# ADC.net
KiCad netlist of a schematic drawn in Altium Designer
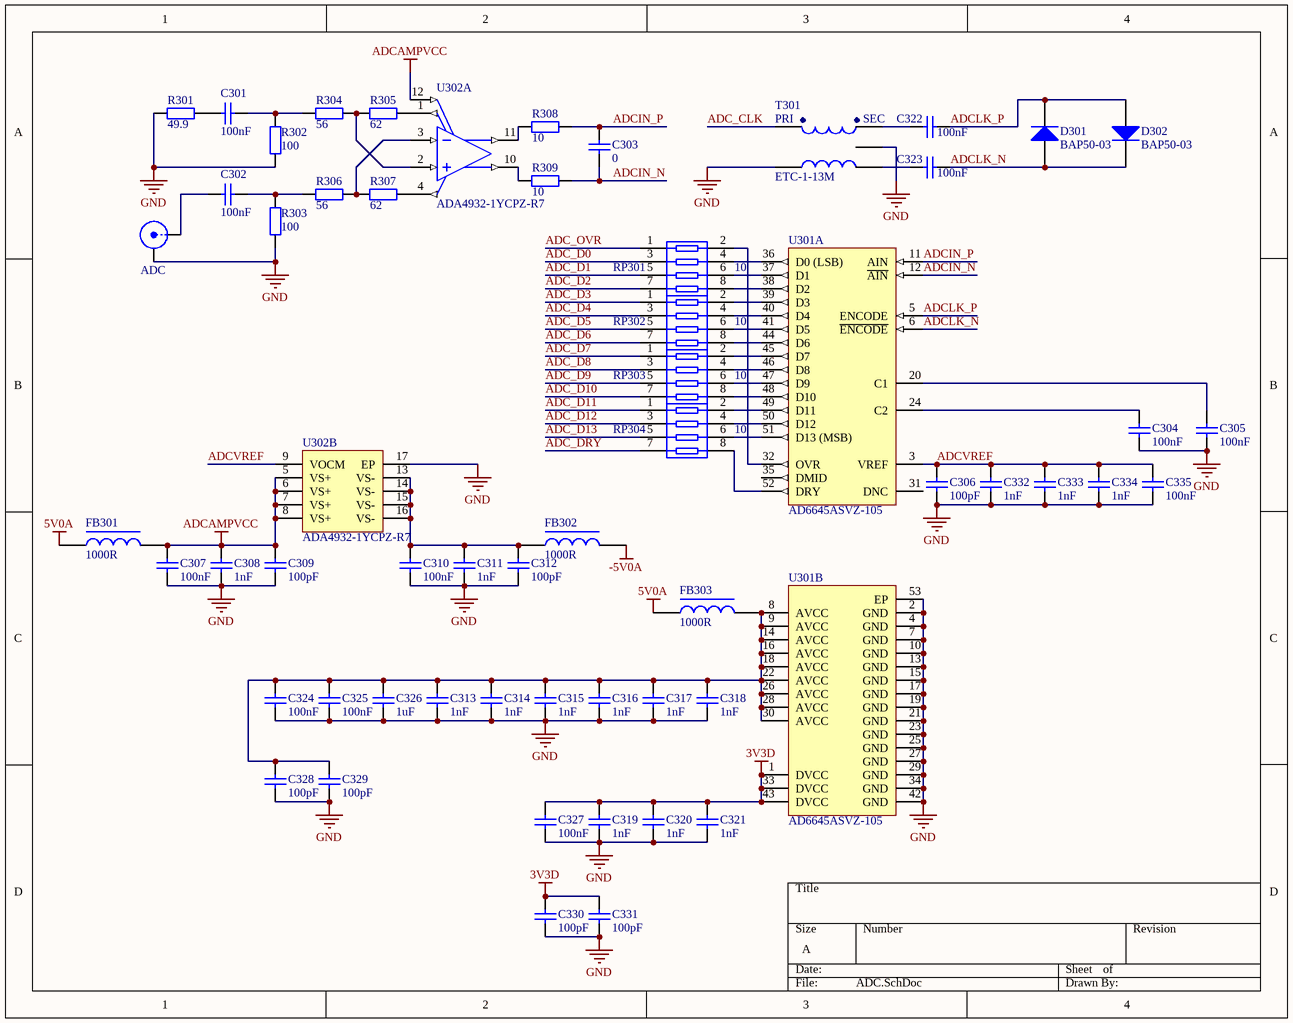
[diagram p0: ADC.SchDoc]

(export (version "E")
  (design (tool "Eeschema 10.0.6"))
  (components
    (comp (ref "ADC")
      (value "SMA")
      (footprint "SMA-V")
      (description "SMA Connector")
      (libsource (lib "SMA") (part "SMA"))
    )
    (comp (ref "C301")
      (value "100nF")
      (footprint "0402C")
      (description "MLCC")
      (libsource (lib "Misc") (part "MLCC"))
    )
    (comp (ref "C302")
      (value "100nF")
      (footprint "0402C")
      (description "MLCC")
      (libsource (lib "Misc") (part "MLCC"))
    )
    (comp (ref "C303")
      (value "0")
      (footprint "0402C")
      (description "MLCC")
      (libsource (lib "Misc") (part "MLCC"))
    )
    (comp (ref "C304")
      (value "100nF")
      (footprint "0402C")
      (description "MLCC")
      (libsource (lib "Misc") (part "MLCC"))
    )
    (comp (ref "C305")
      (value "100nF")
      (footprint "0402C")
      (description "MLCC")
      (libsource (lib "Misc") (part "MLCC"))
    )
    (comp (ref "C306")
      (value "100pF")
      (footprint "0402C")
      (description "MLCC")
      (libsource (lib "Misc") (part "MLCC"))
    )
    (comp (ref "C307")
      (value "100nF")
      (footprint "0603C")
      (description "MLCC")
      (libsource (lib "Misc") (part "MLCC"))
    )
    (comp (ref "C308")
      (value "1nF")
      (footprint "0402C")
      (description "MLCC")
      (libsource (lib "Misc") (part "MLCC"))
    )
    (comp (ref "C309")
      (value "100pF")
      (footprint "0402C")
      (description "MLCC")
      (libsource (lib "Misc") (part "MLCC"))
    )
    (comp (ref "C310")
      (value "100nF")
      (footprint "0603C")
      (description "MLCC")
      (libsource (lib "Misc") (part "MLCC"))
    )
    (comp (ref "C311")
      (value "1nF")
      (footprint "0402C")
      (description "MLCC")
      (libsource (lib "Misc") (part "MLCC"))
    )
    (comp (ref "C312")
      (value "100pF")
      (footprint "0402C")
      (description "MLCC")
      (libsource (lib "Misc") (part "MLCC"))
    )
    (comp (ref "C313")
      (value "1nF")
      (footprint "0402C")
      (description "MLCC")
      (libsource (lib "Misc") (part "MLCC"))
    )
    (comp (ref "C314")
      (value "1nF")
      (footprint "0402C")
      (description "MLCC")
      (libsource (lib "Misc") (part "MLCC"))
    )
    (comp (ref "C315")
      (value "1nF")
      (footprint "0402C")
      (description "MLCC")
      (libsource (lib "Misc") (part "MLCC"))
    )
    (comp (ref "C316")
      (value "1nF")
      (footprint "0402C")
      (description "MLCC")
      (libsource (lib "Misc") (part "MLCC"))
    )
    (comp (ref "C317")
      (value "1nF")
      (footprint "0402C")
      (description "MLCC")
      (libsource (lib "Misc") (part "MLCC"))
    )
    (comp (ref "C318")
      (value "1nF")
      (footprint "0402C")
      (description "MLCC")
      (libsource (lib "Misc") (part "MLCC"))
    )
    (comp (ref "C319")
      (value "1nF")
      (footprint "0402C")
      (description "MLCC")
      (libsource (lib "Misc") (part "MLCC"))
    )
    (comp (ref "C320")
      (value "1nF")
      (footprint "0402C")
      (description "MLCC")
      (libsource (lib "Misc") (part "MLCC"))
    )
    (comp (ref "C321")
      (value "1nF")
      (footprint "0402C")
      (description "MLCC")
      (libsource (lib "Misc") (part "MLCC"))
    )
    (comp (ref "C322")
      (value "100nF")
      (footprint "0402C")
      (description "MLCC")
      (libsource (lib "Misc") (part "MLCC"))
    )
    (comp (ref "C323")
      (value "100nF")
      (footprint "0402C")
      (description "MLCC")
      (libsource (lib "Misc") (part "MLCC"))
    )
    (comp (ref "C324")
      (value "100nF")
      (footprint "0603C")
      (description "MLCC")
      (libsource (lib "Misc") (part "MLCC"))
    )
    (comp (ref "C325")
      (value "100nF")
      (footprint "0603C")
      (description "MLCC")
      (libsource (lib "Misc") (part "MLCC"))
    )
    (comp (ref "C326")
      (value "1uF")
      (footprint "0603C")
      (description "MLCC")
      (libsource (lib "Misc") (part "MLCC"))
    )
    (comp (ref "C327")
      (value "100nF")
      (footprint "0603C")
      (description "MLCC")
      (libsource (lib "Misc") (part "MLCC"))
    )
    (comp (ref "C328")
      (value "100pF")
      (footprint "0402C")
      (description "MLCC")
      (libsource (lib "Misc") (part "MLCC"))
    )
    (comp (ref "C329")
      (value "100pF")
      (footprint "0402C")
      (description "MLCC")
      (libsource (lib "Misc") (part "MLCC"))
    )
    (comp (ref "C330")
      (value "100pF")
      (footprint "0402C")
      (description "MLCC")
      (libsource (lib "Misc") (part "MLCC"))
    )
    (comp (ref "C331")
      (value "100pF")
      (footprint "0402C")
      (description "MLCC")
      (libsource (lib "Misc") (part "MLCC"))
    )
    (comp (ref "C332")
      (value "1nF")
      (footprint "0402C")
      (description "MLCC")
      (libsource (lib "Misc") (part "MLCC"))
    )
    (comp (ref "C333")
      (value "1nF")
      (footprint "0402C")
      (description "MLCC")
      (libsource (lib "Misc") (part "MLCC"))
    )
    (comp (ref "C334")
      (value "1nF")
      (footprint "0402C")
      (description "MLCC")
      (libsource (lib "Misc") (part "MLCC"))
    )
    (comp (ref "C335")
      (value "100nF")
      (footprint "0402C")
      (description "MLCC")
      (libsource (lib "Misc") (part "MLCC"))
    )
    (comp (ref "D301")
      (value "BAP50-03")
      (footprint "SOD323")
      (description "Silicon PIN diode")
      (libsource (lib "Misc") (part "BAP50-03"))
    )
    (comp (ref "D302")
      (value "BAP50-03")
      (footprint "SOD323")
      (description "Silicon PIN diode")
      (libsource (lib "Misc") (part "BAP50-03"))
    )
    (comp (ref "FB301")
      (value "1000R")
      (footprint "0603L")
      (description "FerriteBead")
      (libsource (lib "Misc") (part "FerriteBead"))
    )
    (comp (ref "FB302")
      (value "1000R")
      (footprint "0603L")
      (description "FerriteBead")
      (libsource (lib "Misc") (part "FerriteBead"))
    )
    (comp (ref "FB303")
      (value "1000R")
      (footprint "0603L")
      (description "FerriteBead")
      (libsource (lib "Misc") (part "FerriteBead"))
    )
    (comp (ref "R301")
      (value "49.9")
      (footprint "0402R")
      (description "Resistor")
      (libsource (lib "") (part "Resistor_1"))
    )
    (comp (ref "R302")
      (value "100")
      (footprint "0402R")
      (description "Resistor")
      (libsource (lib "Misc") (part "Resistor"))
    )
    (comp (ref "R303")
      (value "100")
      (footprint "0402R")
      (description "Resistor")
      (libsource (lib "Misc") (part "Resistor"))
    )
    (comp (ref "R304")
      (value "56")
      (footprint "0402R")
      (description "Resistor")
      (libsource (lib "") (part "Resistor_1"))
    )
    (comp (ref "R305")
      (value "62")
      (footprint "0402R")
      (description "Resistor")
      (libsource (lib "") (part "Resistor_1"))
    )
    (comp (ref "R306")
      (value "56")
      (footprint "0402R")
      (description "Resistor")
      (libsource (lib "") (part "Resistor_1"))
    )
    (comp (ref "R307")
      (value "62")
      (footprint "0402R")
      (description "Resistor")
      (libsource (lib "") (part "Resistor_1"))
    )
    (comp (ref "R308")
      (value "10")
      (footprint "0402R")
      (description "Resistor")
      (libsource (lib "") (part "Resistor_1"))
    )
    (comp (ref "R309")
      (value "10")
      (footprint "0402R")
      (description "Resistor")
      (libsource (lib "") (part "Resistor_1"))
    )
    (comp (ref "RP301")
      (value "10")
      (footprint "8P4R_0402")
      (description "Isolated Resistor Network")
      (fields (field (name "Comment") "Res Pack"))
      (libsource (lib "Misc") (part "Res Pack"))
    )
    (comp (ref "RP302")
      (value "10")
      (footprint "8P4R_0402")
      (description "Isolated Resistor Network")
      (fields (field (name "Comment") "Res Pack"))
      (libsource (lib "Misc") (part "Res Pack"))
    )
    (comp (ref "RP303")
      (value "10")
      (footprint "8P4R_0402")
      (description "Isolated Resistor Network")
      (fields (field (name "Comment") "Res Pack"))
      (libsource (lib "Misc") (part "Res Pack"))
    )
    (comp (ref "RP304")
      (value "10")
      (footprint "8P4R_0402")
      (description "Isolated Resistor Network")
      (fields (field (name "Comment") "Res Pack"))
      (libsource (lib "Misc") (part "Res Pack"))
    )
    (comp (ref "T301")
      (value "ETC-1-13M")
      (footprint "ETC1-1-13M")
      (description "RF balun")
      (libsource (lib "ETC1-1-13M") (part "ETC-1-13M"))
    )
    (comp (ref "U301")
      (value "AD6645ASVZ-105")
      (footprint "SV-52-1_N")
      (fields
        (field (name "GENERIC PART NUMBER") "AD6645-105")
        (field (name "MANUFACTURER") "Analog Devices")
      )
      (libsource (lib "Analog Devices Data Converters Analog-to-Digital Converters") (part "AD6645ASVZ-105"))
    )
    (comp (ref "U302")
      (value "ADA4932-1YCPZ-R7")
      (footprint "ADI-CP-16-2_L")
      (fields (field (name "MANUFACTURER") "Analog Devices"))
      (libsource (lib "ADA4932") (part "ADA4932-1YCPZ"))
    )
  )
  (nets
    (net (code "1") (name "-5V0A") (class "Default")
      (node (ref "FB302") (pin "2") (pinfunction "2_2") (pintype "passive"))
    )
    (net (code "2") (name "/ADCIN_N") (class "Default")
      (node (ref "C303") (pin "1") (pinfunction "1_1") (pintype "passive"))
      (node (ref "R309") (pin "2") (pinfunction "2_2") (pintype "passive"))
      (node (ref "U301") (pin "12") (pinfunction "~{AIN}_12") (pintype "input"))
    )
    (net (code "3") (name "/ADCIN_P") (class "Default")
      (node (ref "C303") (pin "2") (pinfunction "2_2") (pintype "passive"))
      (node (ref "R308") (pin "2") (pinfunction "2_2") (pintype "passive"))
      (node (ref "U301") (pin "11") (pinfunction "AIN_11") (pintype "input"))
    )
    (net (code "4") (name "/ADCLK_N") (class "Default")
      (node (ref "C323") (pin "2") (pinfunction "2_2") (pintype "passive"))
      (node (ref "D301") (pin "1") (pinfunction "A_1") (pintype "passive"))
      (node (ref "D302") (pin "2") (pinfunction "K_2") (pintype "passive"))
      (node (ref "U301") (pin "6") (pinfunction "~{ENCODE}_6") (pintype "input"))
    )
    (net (code "5") (name "/ADCLK_P") (class "Default")
      (node (ref "C322") (pin "2") (pinfunction "2_2") (pintype "passive"))
      (node (ref "D301") (pin "2") (pinfunction "K_2") (pintype "passive"))
      (node (ref "D302") (pin "1") (pinfunction "A_1") (pintype "passive"))
      (node (ref "U301") (pin "5") (pinfunction "ENCODE_5") (pintype "input"))
    )
    (net (code "6") (name "/ADCVREF") (class "Default")
      (node (ref "C306") (pin "2") (pinfunction "2_2") (pintype "passive"))
      (node (ref "C332") (pin "2") (pinfunction "2_2") (pintype "passive"))
      (node (ref "C333") (pin "2") (pinfunction "2_2") (pintype "passive"))
      (node (ref "C334") (pin "2") (pinfunction "2_2") (pintype "passive"))
      (node (ref "C335") (pin "2") (pinfunction "2_2") (pintype "passive"))
      (node (ref "U301") (pin "3") (pinfunction "VREF_3") (pintype "passive"))
      (node (ref "U302") (pin "9") (pinfunction "VOCM_9") (pintype "power_in"))
    )
    (net (code "7") (name "/ADC_CLK") (class "Default")
      (node (ref "T301") (pin "1") (pinfunction "PD_1") (pintype "passive"))
    )
    (net (code "8") (name "/ADC_D0") (class "Default")
      (node (ref "RP301") (pin "3") (pinfunction "3_3") (pintype "passive"))
    )
    (net (code "9") (name "/ADC_D1") (class "Default")
      (node (ref "RP301") (pin "5") (pinfunction "5_5") (pintype "passive"))
    )
    (net (code "10") (name "/ADC_D2") (class "Default")
      (node (ref "RP301") (pin "7") (pinfunction "7_7") (pintype "passive"))
    )
    (net (code "11") (name "/ADC_D3") (class "Default")
      (node (ref "RP302") (pin "1") (pinfunction "1_1") (pintype "passive"))
    )
    (net (code "12") (name "/ADC_D4") (class "Default")
      (node (ref "RP302") (pin "3") (pinfunction "3_3") (pintype "passive"))
    )
    (net (code "13") (name "/ADC_D5") (class "Default")
      (node (ref "RP302") (pin "5") (pinfunction "5_5") (pintype "passive"))
    )
    (net (code "14") (name "/ADC_D6") (class "Default")
      (node (ref "RP302") (pin "7") (pinfunction "7_7") (pintype "passive"))
    )
    (net (code "15") (name "/ADC_D7") (class "Default")
      (node (ref "RP303") (pin "1") (pinfunction "1_1") (pintype "passive"))
    )
    (net (code "16") (name "/ADC_D8") (class "Default")
      (node (ref "RP303") (pin "3") (pinfunction "3_3") (pintype "passive"))
    )
    (net (code "17") (name "/ADC_D9") (class "Default")
      (node (ref "RP303") (pin "5") (pinfunction "5_5") (pintype "passive"))
    )
    (net (code "18") (name "/ADC_D10") (class "Default")
      (node (ref "RP303") (pin "7") (pinfunction "7_7") (pintype "passive"))
    )
    (net (code "19") (name "/ADC_D11") (class "Default")
      (node (ref "RP304") (pin "1") (pinfunction "1_1") (pintype "passive"))
    )
    (net (code "20") (name "/ADC_D12") (class "Default")
      (node (ref "RP304") (pin "3") (pinfunction "3_3") (pintype "passive"))
    )
    (net (code "21") (name "/ADC_D13") (class "Default")
      (node (ref "RP304") (pin "5") (pinfunction "5_5") (pintype "passive"))
    )
    (net (code "22") (name "/ADC_DRY") (class "Default")
      (node (ref "RP304") (pin "7") (pinfunction "7_7") (pintype "passive"))
    )
    (net (code "23") (name "/ADC_OVR") (class "Default")
      (node (ref "RP301") (pin "1") (pinfunction "1_1") (pintype "passive"))
    )
    (net (code "24") (name "3V3D") (class "Default")
      (node (ref "C319") (pin "2") (pinfunction "2_2") (pintype "passive"))
      (node (ref "C320") (pin "2") (pinfunction "2_2") (pintype "passive"))
      (node (ref "C321") (pin "2") (pinfunction "2_2") (pintype "passive"))
      (node (ref "C327") (pin "2") (pinfunction "2_2") (pintype "passive"))
      (node (ref "C330") (pin "2") (pinfunction "2_2") (pintype "passive"))
      (node (ref "C331") (pin "2") (pinfunction "2_2") (pintype "passive"))
      (node (ref "U301") (pin "1") (pinfunction "DVCC_1") (pintype "power_in"))
      (node (ref "U301") (pin "33") (pinfunction "DVCC_33") (pintype "power_in"))
      (node (ref "U301") (pin "43") (pinfunction "DVCC_43") (pintype "power_in"))
    )
    (net (code "25") (name "5V0A") (class "Default")
      (node (ref "FB301") (pin "1") (pinfunction "1_1") (pintype "passive"))
      (node (ref "FB303") (pin "1") (pinfunction "1_1") (pintype "passive"))
    )
    (net (code "26") (name "ADCAMPVCC") (class "Default")
      (node (ref "C307") (pin "2") (pinfunction "2_2") (pintype "passive"))
      (node (ref "C308") (pin "2") (pinfunction "2_2") (pintype "passive"))
      (node (ref "C309") (pin "2") (pinfunction "2_2") (pintype "passive"))
      (node (ref "FB301") (pin "2") (pinfunction "2_2") (pintype "passive"))
      (node (ref "U302") (pin "12") (pinfunction "~{PD}_12") (pintype "input"))
      (node (ref "U302") (pin "5") (pinfunction "VS+_5") (pintype "power_in"))
      (node (ref "U302") (pin "6") (pinfunction "VS+_6") (pintype "power_in"))
      (node (ref "U302") (pin "7") (pinfunction "VS+_7") (pintype "power_in"))
      (node (ref "U302") (pin "8") (pinfunction "VS+_8") (pintype "power_in"))
    )
    (net (code "27") (name "GND") (class "Default")
      (node (ref "ADC") (pin "2") (pinfunction "Y_2") (pintype "passive"))
      (node (ref "C304") (pin "1") (pinfunction "1_1") (pintype "passive"))
      (node (ref "C305") (pin "1") (pinfunction "1_1") (pintype "passive"))
      (node (ref "C306") (pin "1") (pinfunction "1_1") (pintype "passive"))
      (node (ref "C307") (pin "1") (pinfunction "1_1") (pintype "passive"))
      (node (ref "C308") (pin "1") (pinfunction "1_1") (pintype "passive"))
      (node (ref "C309") (pin "1") (pinfunction "1_1") (pintype "passive"))
      (node (ref "C310") (pin "1") (pinfunction "1_1") (pintype "passive"))
      (node (ref "C311") (pin "1") (pinfunction "1_1") (pintype "passive"))
      (node (ref "C312") (pin "1") (pinfunction "1_1") (pintype "passive"))
      (node (ref "C313") (pin "1") (pinfunction "1_1") (pintype "passive"))
      (node (ref "C314") (pin "1") (pinfunction "1_1") (pintype "passive"))
      (node (ref "C315") (pin "1") (pinfunction "1_1") (pintype "passive"))
      (node (ref "C316") (pin "1") (pinfunction "1_1") (pintype "passive"))
      (node (ref "C317") (pin "1") (pinfunction "1_1") (pintype "passive"))
      (node (ref "C318") (pin "1") (pinfunction "1_1") (pintype "passive"))
      (node (ref "C319") (pin "1") (pinfunction "1_1") (pintype "passive"))
      (node (ref "C320") (pin "1") (pinfunction "1_1") (pintype "passive"))
      (node (ref "C321") (pin "1") (pinfunction "1_1") (pintype "passive"))
      (node (ref "C324") (pin "1") (pinfunction "1_1") (pintype "passive"))
      (node (ref "C325") (pin "1") (pinfunction "1_1") (pintype "passive"))
      (node (ref "C326") (pin "1") (pinfunction "1_1") (pintype "passive"))
      (node (ref "C327") (pin "1") (pinfunction "1_1") (pintype "passive"))
      (node (ref "C328") (pin "1") (pinfunction "1_1") (pintype "passive"))
      (node (ref "C329") (pin "1") (pinfunction "1_1") (pintype "passive"))
      (node (ref "C330") (pin "1") (pinfunction "1_1") (pintype "passive"))
      (node (ref "C331") (pin "1") (pinfunction "1_1") (pintype "passive"))
      (node (ref "C332") (pin "1") (pinfunction "1_1") (pintype "passive"))
      (node (ref "C333") (pin "1") (pinfunction "1_1") (pintype "passive"))
      (node (ref "C334") (pin "1") (pinfunction "1_1") (pintype "passive"))
      (node (ref "C335") (pin "1") (pinfunction "1_1") (pintype "passive"))
      (node (ref "R301") (pin "1") (pinfunction "1_1") (pintype "passive"))
      (node (ref "R302") (pin "1") (pinfunction "1_1") (pintype "passive"))
      (node (ref "R303") (pin "1") (pinfunction "1_1") (pintype "passive"))
      (node (ref "T301") (pin "2") (pinfunction "P_2") (pintype "passive"))
      (node (ref "T301") (pin "4") (pinfunction "G_4") (pintype "passive"))
      (node (ref "U301") (pin "10") (pinfunction "GND_10") (pintype "power_in"))
      (node (ref "U301") (pin "13") (pinfunction "GND_13") (pintype "power_in"))
      (node (ref "U301") (pin "15") (pinfunction "GND_15") (pintype "power_in"))
      (node (ref "U301") (pin "17") (pinfunction "GND_17") (pintype "power_in"))
      (node (ref "U301") (pin "19") (pinfunction "GND_19") (pintype "power_in"))
      (node (ref "U301") (pin "2") (pinfunction "GND_2") (pintype "power_in"))
      (node (ref "U301") (pin "21") (pinfunction "GND_21") (pintype "power_in"))
      (node (ref "U301") (pin "23") (pinfunction "GND_23") (pintype "power_in"))
      (node (ref "U301") (pin "25") (pinfunction "GND_25") (pintype "power_in"))
      (node (ref "U301") (pin "27") (pinfunction "GND_27") (pintype "power_in"))
      (node (ref "U301") (pin "29") (pinfunction "GND_29") (pintype "power_in"))
      (node (ref "U301") (pin "34") (pinfunction "GND_34") (pintype "power_in"))
      (node (ref "U301") (pin "4") (pinfunction "GND_4") (pintype "power_in"))
      (node (ref "U301") (pin "42") (pinfunction "GND_42") (pintype "power_in"))
      (node (ref "U301") (pin "53") (pinfunction "EP_53") (pintype "power_in"))
      (node (ref "U301") (pin "7") (pinfunction "GND_7") (pintype "power_in"))
      (node (ref "U302") (pin "17") (pinfunction "EP_17") (pintype "power_in"))
    )
    (net (code "28") (name "Net-(ADC-X)") (class "Default")
      (node (ref "ADC") (pin "1") (pinfunction "X_1") (pintype "passive"))
      (node (ref "C302") (pin "1") (pinfunction "1_1") (pintype "passive"))
    )
    (net (code "29") (name "Net-(C301-Pad1)") (class "Default")
      (node (ref "C301") (pin "1") (pinfunction "1_1") (pintype "passive"))
      (node (ref "R301") (pin "2") (pinfunction "2_2") (pintype "passive"))
    )
    (net (code "30") (name "Net-(C301-Pad2)") (class "Default")
      (node (ref "C301") (pin "2") (pinfunction "2_2") (pintype "passive"))
      (node (ref "R302") (pin "2") (pinfunction "2_2") (pintype "passive"))
      (node (ref "R304") (pin "1") (pinfunction "1_1") (pintype "passive"))
    )
    (net (code "31") (name "Net-(C302-Pad2)") (class "Default")
      (node (ref "C302") (pin "2") (pinfunction "2_2") (pintype "passive"))
      (node (ref "R303") (pin "2") (pinfunction "2_2") (pintype "passive"))
      (node (ref "R306") (pin "1") (pinfunction "1_1") (pintype "passive"))
    )
    (net (code "32") (name "Net-(C310-Pad2)") (class "Default")
      (node (ref "C310") (pin "2") (pinfunction "2_2") (pintype "passive"))
      (node (ref "C311") (pin "2") (pinfunction "2_2") (pintype "passive"))
      (node (ref "C312") (pin "2") (pinfunction "2_2") (pintype "passive"))
      (node (ref "FB302") (pin "1") (pinfunction "1_1") (pintype "passive"))
      (node (ref "U302") (pin "13") (pinfunction "VS-_13") (pintype "power_in"))
      (node (ref "U302") (pin "14") (pinfunction "VS-_14") (pintype "power_in"))
      (node (ref "U302") (pin "15") (pinfunction "VS-_15") (pintype "power_in"))
      (node (ref "U302") (pin "16") (pinfunction "VS-_16") (pintype "power_in"))
    )
    (net (code "33") (name "Net-(C313-Pad2)") (class "Default")
      (node (ref "C313") (pin "2") (pinfunction "2_2") (pintype "passive"))
      (node (ref "C314") (pin "2") (pinfunction "2_2") (pintype "passive"))
      (node (ref "C315") (pin "2") (pinfunction "2_2") (pintype "passive"))
      (node (ref "C316") (pin "2") (pinfunction "2_2") (pintype "passive"))
      (node (ref "C317") (pin "2") (pinfunction "2_2") (pintype "passive"))
      (node (ref "C318") (pin "2") (pinfunction "2_2") (pintype "passive"))
      (node (ref "C324") (pin "2") (pinfunction "2_2") (pintype "passive"))
      (node (ref "C325") (pin "2") (pinfunction "2_2") (pintype "passive"))
      (node (ref "C326") (pin "2") (pinfunction "2_2") (pintype "passive"))
      (node (ref "C328") (pin "2") (pinfunction "2_2") (pintype "passive"))
      (node (ref "C329") (pin "2") (pinfunction "2_2") (pintype "passive"))
      (node (ref "FB303") (pin "2") (pinfunction "2_2") (pintype "passive"))
      (node (ref "U301") (pin "14") (pinfunction "AVCC_14") (pintype "power_in"))
      (node (ref "U301") (pin "16") (pinfunction "AVCC_16") (pintype "power_in"))
      (node (ref "U301") (pin "18") (pinfunction "AVCC_18") (pintype "power_in"))
      (node (ref "U301") (pin "22") (pinfunction "AVCC_22") (pintype "power_in"))
      (node (ref "U301") (pin "26") (pinfunction "AVCC_26") (pintype "power_in"))
      (node (ref "U301") (pin "28") (pinfunction "AVCC_28") (pintype "power_in"))
      (node (ref "U301") (pin "30") (pinfunction "AVCC_30") (pintype "power_in"))
      (node (ref "U301") (pin "8") (pinfunction "AVCC_8") (pintype "power_in"))
      (node (ref "U301") (pin "9") (pinfunction "AVCC_9") (pintype "power_in"))
    )
    (net (code "34") (name "Net-(T301-S)") (class "Default")
      (node (ref "C323") (pin "1") (pinfunction "1_1") (pintype "passive"))
      (node (ref "T301") (pin "3") (pinfunction "S_3") (pintype "passive"))
    )
    (net (code "35") (name "Net-(T301-SD)") (class "Default")
      (node (ref "C322") (pin "1") (pinfunction "1_1") (pintype "passive"))
      (node (ref "T301") (pin "5") (pinfunction "SD_5") (pintype "passive"))
    )
    (net (code "36") (name "Net-(U301A-C1)") (class "Default")
      (node (ref "C305") (pin "2") (pinfunction "2_2") (pintype "passive"))
      (node (ref "U301") (pin "20") (pinfunction "C1_20") (pintype "passive"))
    )
    (net (code "37") (name "Net-(U301A-C2)") (class "Default")
      (node (ref "C304") (pin "2") (pinfunction "2_2") (pintype "passive"))
      (node (ref "U301") (pin "24") (pinfunction "C2_24") (pintype "passive"))
    )
    (net (code "38") (name "Net-(U301A-D0_(LSB))") (class "Default")
      (node (ref "RP301") (pin "4") (pinfunction "4_4") (pintype "passive"))
      (node (ref "U301") (pin "36") (pinfunction "D0_(LSB)_36") (pintype "output"))
    )
    (net (code "39") (name "Net-(U301A-D1)") (class "Default")
      (node (ref "RP301") (pin "6") (pinfunction "6_6") (pintype "passive"))
      (node (ref "U301") (pin "37") (pinfunction "D1_37") (pintype "output"))
    )
    (net (code "40") (name "Net-(U301A-D2)") (class "Default")
      (node (ref "RP301") (pin "8") (pinfunction "8_8") (pintype "passive"))
      (node (ref "U301") (pin "38") (pinfunction "D2_38") (pintype "output"))
    )
    (net (code "41") (name "Net-(U301A-D3)") (class "Default")
      (node (ref "RP302") (pin "2") (pinfunction "2_2") (pintype "passive"))
      (node (ref "U301") (pin "39") (pinfunction "D3_39") (pintype "output"))
    )
    (net (code "42") (name "Net-(U301A-D4)") (class "Default")
      (node (ref "RP302") (pin "4") (pinfunction "4_4") (pintype "passive"))
      (node (ref "U301") (pin "40") (pinfunction "D4_40") (pintype "output"))
    )
    (net (code "43") (name "Net-(U301A-D5)") (class "Default")
      (node (ref "RP302") (pin "6") (pinfunction "6_6") (pintype "passive"))
      (node (ref "U301") (pin "41") (pinfunction "D5_41") (pintype "output"))
    )
    (net (code "44") (name "Net-(U301A-D6)") (class "Default")
      (node (ref "RP302") (pin "8") (pinfunction "8_8") (pintype "passive"))
      (node (ref "U301") (pin "44") (pinfunction "D6_44") (pintype "output"))
    )
    (net (code "45") (name "Net-(U301A-D7)") (class "Default")
      (node (ref "RP303") (pin "2") (pinfunction "2_2") (pintype "passive"))
      (node (ref "U301") (pin "45") (pinfunction "D7_45") (pintype "output"))
    )
    (net (code "46") (name "Net-(U301A-D8)") (class "Default")
      (node (ref "RP303") (pin "4") (pinfunction "4_4") (pintype "passive"))
      (node (ref "U301") (pin "46") (pinfunction "D8_46") (pintype "output"))
    )
    (net (code "47") (name "Net-(U301A-D9)") (class "Default")
      (node (ref "RP303") (pin "6") (pinfunction "6_6") (pintype "passive"))
      (node (ref "U301") (pin "47") (pinfunction "D9_47") (pintype "output"))
    )
    (net (code "48") (name "Net-(U301A-D10)") (class "Default")
      (node (ref "RP303") (pin "8") (pinfunction "8_8") (pintype "passive"))
      (node (ref "U301") (pin "48") (pinfunction "D10_48") (pintype "output"))
    )
    (net (code "49") (name "Net-(U301A-D11)") (class "Default")
      (node (ref "RP304") (pin "2") (pinfunction "2_2") (pintype "passive"))
      (node (ref "U301") (pin "49") (pinfunction "D11_49") (pintype "output"))
    )
    (net (code "50") (name "Net-(U301A-D12)") (class "Default")
      (node (ref "RP304") (pin "4") (pinfunction "4_4") (pintype "passive"))
      (node (ref "U301") (pin "50") (pinfunction "D12_50") (pintype "output"))
    )
    (net (code "51") (name "Net-(U301A-D13_(MSB))") (class "Default")
      (node (ref "RP304") (pin "6") (pinfunction "6_6") (pintype "passive"))
      (node (ref "U301") (pin "51") (pinfunction "D13_(MSB)_51") (pintype "output"))
    )
    (net (code "52") (name "Net-(U301A-DRY)") (class "Default")
      (node (ref "RP304") (pin "8") (pinfunction "8_8") (pintype "passive"))
      (node (ref "U301") (pin "52") (pinfunction "DRY_52") (pintype "output"))
    )
    (net (code "53") (name "Net-(U301A-OVR)") (class "Default")
      (node (ref "RP301") (pin "2") (pinfunction "2_2") (pintype "passive"))
      (node (ref "U301") (pin "32") (pinfunction "OVR_32") (pintype "output"))
    )
    (net (code "54") (name "Net-(U302A-FB+)") (class "Default")
      (node (ref "R307") (pin "2") (pinfunction "2_2") (pintype "passive"))
      (node (ref "U302") (pin "4") (pinfunction "FB+_4") (pintype "output"))
    )
    (net (code "55") (name "Net-(U302A-FB-)") (class "Default")
      (node (ref "R305") (pin "2") (pinfunction "2_2") (pintype "passive"))
      (node (ref "U302") (pin "1") (pinfunction "FB-_1") (pintype "output"))
    )
    (net (code "56") (name "Net-(U302A-IN+)") (class "Default")
      (node (ref "R304") (pin "2") (pinfunction "2_2") (pintype "passive"))
      (node (ref "R305") (pin "1") (pinfunction "1_1") (pintype "passive"))
      (node (ref "U302") (pin "2") (pinfunction "IN+_2") (pintype "input"))
    )
    (net (code "57") (name "Net-(U302A-IN-)") (class "Default")
      (node (ref "R306") (pin "2") (pinfunction "2_2") (pintype "passive"))
      (node (ref "R307") (pin "1") (pinfunction "1_1") (pintype "passive"))
      (node (ref "U302") (pin "3") (pinfunction "IN-_3") (pintype "input"))
    )
    (net (code "58") (name "Net-(U302A-OUT+)") (class "Default")
      (node (ref "R309") (pin "1") (pinfunction "1_1") (pintype "passive"))
      (node (ref "U302") (pin "10") (pinfunction "OUT+_10") (pintype "output"))
    )
    (net (code "59") (name "Net-(U302A-OUT-)") (class "Default")
      (node (ref "R308") (pin "1") (pinfunction "1_1") (pintype "passive"))
      (node (ref "U302") (pin "11") (pinfunction "OUT-_11") (pintype "output"))
    )
    (net (code "60") (name "unconnected-(U301A-DMID-Pad35)") (class "Default")
      (node (ref "U301") (pin "35") (pinfunction "DMID_35") (pintype "output"))
    )
    (net (code "61") (name "unconnected-(U301A-DNC-Pad31)") (class "Default")
      (node (ref "U301") (pin "31") (pinfunction "DNC_31") (pintype "passive"))
    )
  )
)
